# Clock.net
KiCad netlist of a schematic drawn in EAGLE
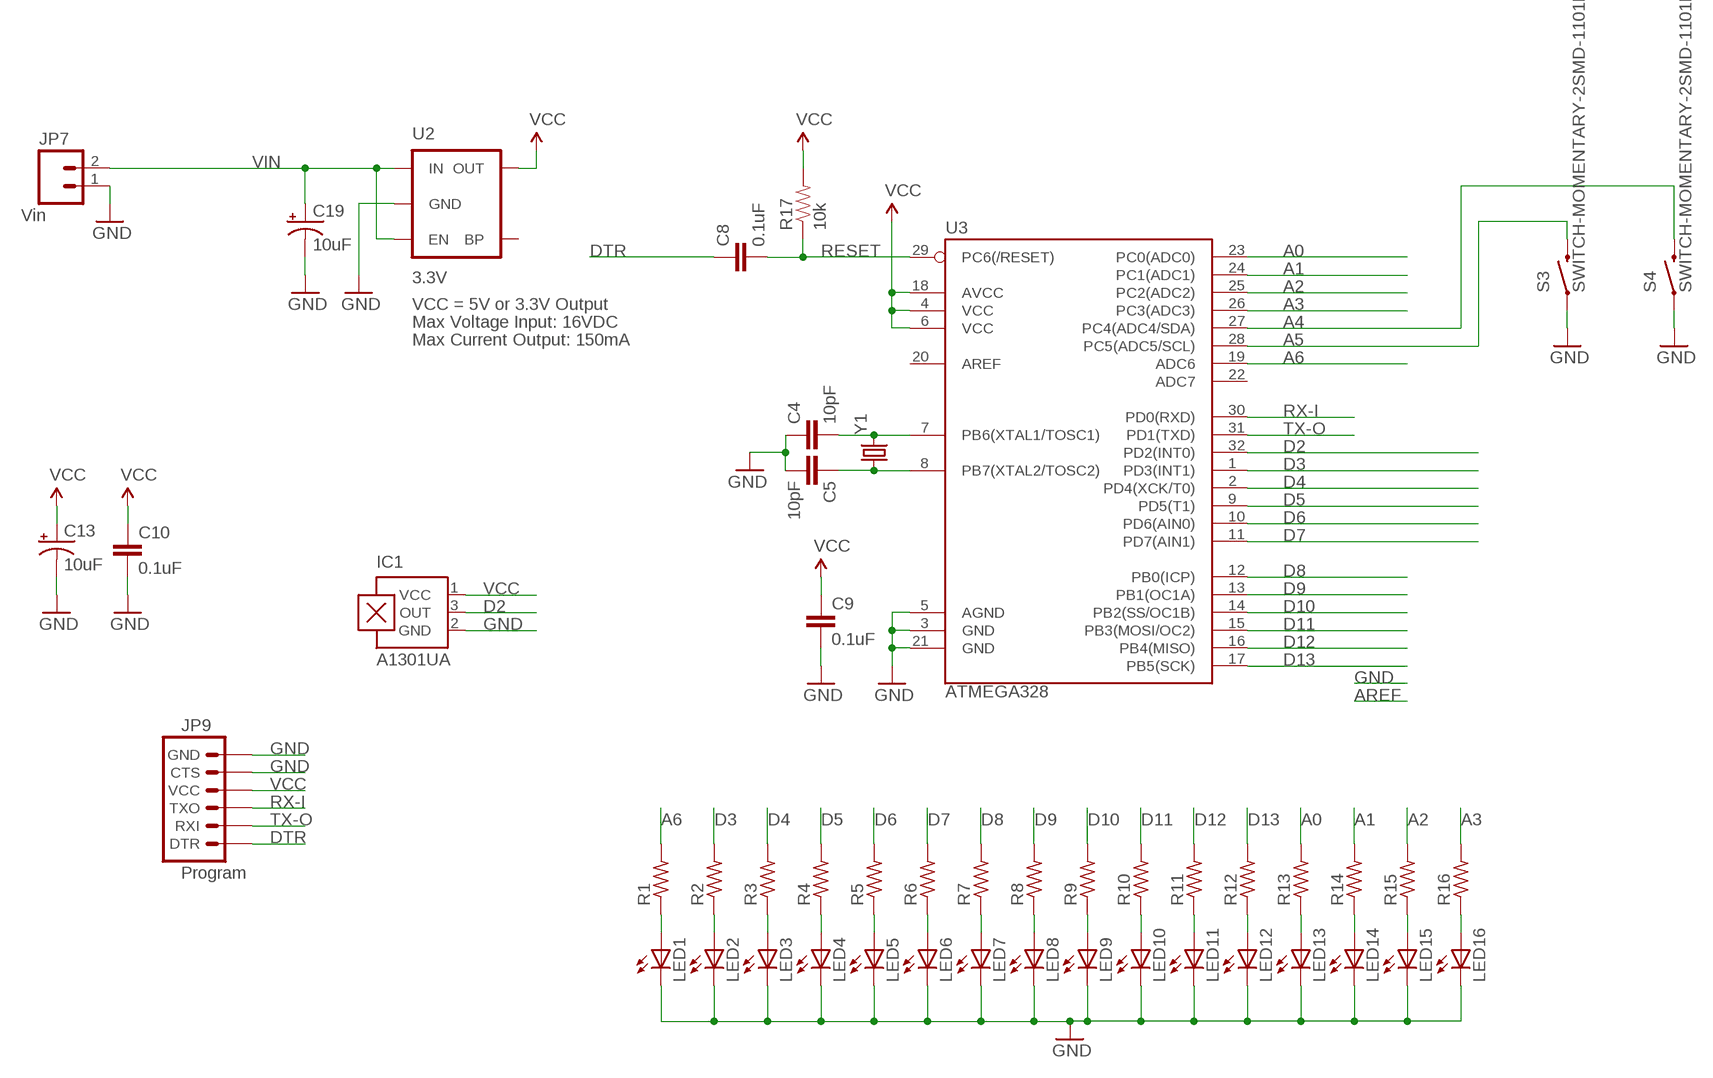
[diagram p0: schematic, sheet 1]

(export (version "E")
  (design (tool "Eeschema 10.0.6"))
  (components
    (comp (ref "C4")
      (value "10pF")
      (footprint "eagle-import:0603-CAP")
      (libsource (lib "eagle-import") (part "CAP0603-CAP"))
    )
    (comp (ref "C5")
      (value "10pF")
      (footprint "eagle-import:0603-CAP")
      (libsource (lib "eagle-import") (part "CAP0603-CAP"))
    )
    (comp (ref "C8")
      (value "0.1uF")
      (footprint "eagle-import:0603-CAP")
      (libsource (lib "eagle-import") (part "CAP0603-CAP"))
    )
    (comp (ref "C9")
      (value "0.1uF")
      (footprint "eagle-import:0603-CAP")
      (libsource (lib "eagle-import") (part "CAP0603-CAP"))
    )
    (comp (ref "C10")
      (value "0.1uF")
      (footprint "eagle-import:0603-CAP")
      (libsource (lib "eagle-import") (part "CAP0603-CAP"))
    )
    (comp (ref "C13")
      (value "10uF")
      (footprint "eagle-import:EIA3216")
      (libsource (lib "eagle-import") (part "CAP_POL1206"))
    )
    (comp (ref "C19")
      (value "10uF")
      (footprint "eagle-import:EIA3216")
      (libsource (lib "eagle-import") (part "CAP_POL1206"))
    )
    (comp (ref "IC1")
      (value "A1301UA")
      (footprint "eagle-import:SIP3-UA")
      (fields (field (name "MF") "ALLEGRO MICROSYSTEMS, INC.") (field (name "MPN") "A1301EUA-T"))
      (libsource (lib "eagle-import") (part "A13?UA01"))
    )
    (comp (ref "JP7")
      (value "Vin")
      (footprint "eagle-import:1X02")
      (libsource (lib "eagle-import") (part "M02PTH"))
    )
    (comp (ref "JP9")
      (value "Program")
      (footprint "eagle-import:1X06-SMD")
      (libsource (lib "eagle-import") (part "ARDUINO_SERIAL_PROGRAMSMD"))
    )
    (comp (ref "LED1")
      (value "LEDCHIPLED_1206")
      (footprint "eagle-import:CHIPLED_1206")
      (libsource (lib "eagle-import") (part "LEDCHIPLED_1206"))
    )
    (comp (ref "LED2")
      (value "LEDCHIPLED_1206")
      (footprint "eagle-import:CHIPLED_1206")
      (libsource (lib "eagle-import") (part "LEDCHIPLED_1206"))
    )
    (comp (ref "LED3")
      (value "LEDCHIPLED_1206")
      (footprint "eagle-import:CHIPLED_1206")
      (libsource (lib "eagle-import") (part "LEDCHIPLED_1206"))
    )
    (comp (ref "LED4")
      (value "LEDCHIPLED_1206")
      (footprint "eagle-import:CHIPLED_1206")
      (libsource (lib "eagle-import") (part "LEDCHIPLED_1206"))
    )
    (comp (ref "LED5")
      (value "LEDCHIPLED_1206")
      (footprint "eagle-import:CHIPLED_1206")
      (libsource (lib "eagle-import") (part "LEDCHIPLED_1206"))
    )
    (comp (ref "LED6")
      (value "LEDCHIPLED_1206")
      (footprint "eagle-import:CHIPLED_1206")
      (libsource (lib "eagle-import") (part "LEDCHIPLED_1206"))
    )
    (comp (ref "LED7")
      (value "LEDCHIPLED_1206")
      (footprint "eagle-import:CHIPLED_1206")
      (libsource (lib "eagle-import") (part "LEDCHIPLED_1206"))
    )
    (comp (ref "LED8")
      (value "LEDCHIPLED_1206")
      (footprint "eagle-import:CHIPLED_1206")
      (libsource (lib "eagle-import") (part "LEDCHIPLED_1206"))
    )
    (comp (ref "LED9")
      (value "LEDCHIPLED_1206")
      (footprint "eagle-import:CHIPLED_1206")
      (libsource (lib "eagle-import") (part "LEDCHIPLED_1206"))
    )
    (comp (ref "LED10")
      (value "LEDCHIPLED_1206")
      (footprint "eagle-import:CHIPLED_1206")
      (libsource (lib "eagle-import") (part "LEDCHIPLED_1206"))
    )
    (comp (ref "LED11")
      (value "LEDCHIPLED_1206")
      (footprint "eagle-import:CHIPLED_1206")
      (libsource (lib "eagle-import") (part "LEDCHIPLED_1206"))
    )
    (comp (ref "LED12")
      (value "LEDCHIPLED_1206")
      (footprint "eagle-import:CHIPLED_1206")
      (libsource (lib "eagle-import") (part "LEDCHIPLED_1206"))
    )
    (comp (ref "LED13")
      (value "LEDCHIPLED_1206")
      (footprint "eagle-import:CHIPLED_1206")
      (libsource (lib "eagle-import") (part "LEDCHIPLED_1206"))
    )
    (comp (ref "LED14")
      (value "LEDCHIPLED_1206")
      (footprint "eagle-import:CHIPLED_1206")
      (libsource (lib "eagle-import") (part "LEDCHIPLED_1206"))
    )
    (comp (ref "LED15")
      (value "LEDCHIPLED_1206")
      (footprint "eagle-import:CHIPLED_1206")
      (libsource (lib "eagle-import") (part "LEDCHIPLED_1206"))
    )
    (comp (ref "LED16")
      (value "LEDCHIPLED_1206")
      (footprint "eagle-import:CHIPLED_1206")
      (libsource (lib "eagle-import") (part "LEDCHIPLED_1206"))
    )
    (comp (ref "R1")
      (value "R-US_R0603")
      (footprint "eagle-import:R0603")
      (libsource (lib "eagle-import") (part "R-US_R0603"))
    )
    (comp (ref "R2")
      (value "R-US_R0603")
      (footprint "eagle-import:R0603")
      (libsource (lib "eagle-import") (part "R-US_R0603"))
    )
    (comp (ref "R3")
      (value "R-US_R0603")
      (footprint "eagle-import:R0603")
      (libsource (lib "eagle-import") (part "R-US_R0603"))
    )
    (comp (ref "R4")
      (value "R-US_R0603")
      (footprint "eagle-import:R0603")
      (libsource (lib "eagle-import") (part "R-US_R0603"))
    )
    (comp (ref "R5")
      (value "R-US_R0603")
      (footprint "eagle-import:R0603")
      (libsource (lib "eagle-import") (part "R-US_R0603"))
    )
    (comp (ref "R6")
      (value "R-US_R0603")
      (footprint "eagle-import:R0603")
      (libsource (lib "eagle-import") (part "R-US_R0603"))
    )
    (comp (ref "R7")
      (value "R-US_R0603")
      (footprint "eagle-import:R0603")
      (libsource (lib "eagle-import") (part "R-US_R0603"))
    )
    (comp (ref "R8")
      (value "R-US_R0603")
      (footprint "eagle-import:R0603")
      (libsource (lib "eagle-import") (part "R-US_R0603"))
    )
    (comp (ref "R9")
      (value "R-US_R0603")
      (footprint "eagle-import:R0603")
      (libsource (lib "eagle-import") (part "R-US_R0603"))
    )
    (comp (ref "R10")
      (value "R-US_R0603")
      (footprint "eagle-import:R0603")
      (libsource (lib "eagle-import") (part "R-US_R0603"))
    )
    (comp (ref "R11")
      (value "R-US_R0603")
      (footprint "eagle-import:R0603")
      (libsource (lib "eagle-import") (part "R-US_R0603"))
    )
    (comp (ref "R12")
      (value "R-US_R0603")
      (footprint "eagle-import:R0603")
      (libsource (lib "eagle-import") (part "R-US_R0603"))
    )
    (comp (ref "R13")
      (value "R-US_R0603")
      (footprint "eagle-import:R0603")
      (libsource (lib "eagle-import") (part "R-US_R0603"))
    )
    (comp (ref "R14")
      (value "R-US_R0603")
      (footprint "eagle-import:R0603")
      (libsource (lib "eagle-import") (part "R-US_R0603"))
    )
    (comp (ref "R15")
      (value "R-US_R0603")
      (footprint "eagle-import:R0603")
      (libsource (lib "eagle-import") (part "R-US_R0603"))
    )
    (comp (ref "R16")
      (value "R-US_R0603")
      (footprint "eagle-import:R0603")
      (libsource (lib "eagle-import") (part "R-US_R0603"))
    )
    (comp (ref "R17")
      (value "10k")
      (footprint "eagle-import:0603-RES")
      (libsource (lib "eagle-import") (part "RESISTOR0603-RES"))
    )
    (comp (ref "S3")
      (value "SWITCH-MOMENTARY-2SMD-1101NE")
      (footprint "eagle-import:TACTILE-SWITCH-1101NE")
      (libsource (lib "eagle-import") (part "SWITCH-MOMENTARY-2SMD-1101NE"))
    )
    (comp (ref "S4")
      (value "SWITCH-MOMENTARY-2SMD-1101NE")
      (footprint "eagle-import:TACTILE-SWITCH-1101NE")
      (libsource (lib "eagle-import") (part "SWITCH-MOMENTARY-2SMD-1101NE"))
    )
    (comp (ref "U2")
      (value "3.3V")
      (footprint "eagle-import:SOT23-5")
      (libsource (lib "eagle-import") (part "V_REG_LDOSMD"))
    )
    (comp (ref "U3")
      (value "ATMEGA328")
      (footprint "eagle-import:TQFP32-08")
      (libsource (lib "eagle-import") (part "ATMEGA168"))
    )
    (comp (ref "Y1")
      (value "CRYSTAL5X3")
      (footprint "eagle-import:CRYSTAL-SMD-5X3")
      (libsource (lib "eagle-import") (part "CRYSTAL5X3"))
    )
  )
  (nets
    (net (code "1") (name "/A0") (class "Default")
      (node (ref "R13") (pin "2") (pinfunction "2_2") (pintype "passive"))
      (node (ref "U3") (pin "23") (pinfunction "PC0(ADC0)_23") (pintype "bidirectional"))
    )
    (net (code "2") (name "/A1") (class "Default")
      (node (ref "R14") (pin "2") (pinfunction "2_2") (pintype "passive"))
      (node (ref "U3") (pin "24") (pinfunction "PC1(ADC1)_24") (pintype "bidirectional"))
    )
    (net (code "3") (name "/A2") (class "Default")
      (node (ref "R15") (pin "2") (pinfunction "2_2") (pintype "passive"))
      (node (ref "U3") (pin "25") (pinfunction "PC2(ADC2)_25") (pintype "bidirectional"))
    )
    (net (code "4") (name "/A3") (class "Default")
      (node (ref "R16") (pin "2") (pinfunction "2_2") (pintype "passive"))
      (node (ref "U3") (pin "26") (pinfunction "PC3(ADC3)_26") (pintype "bidirectional"))
    )
    (net (code "5") (name "/A4") (class "Default")
      (node (ref "S4") (pin "2") (pinfunction "2_2") (pintype "passive"))
      (node (ref "U3") (pin "27") (pinfunction "PC4(ADC4/SDA)_27") (pintype "bidirectional"))
    )
    (net (code "6") (name "/A5") (class "Default")
      (node (ref "S3") (pin "2") (pinfunction "2_2") (pintype "passive"))
      (node (ref "U3") (pin "28") (pinfunction "PC5(ADC5/SCL)_28") (pintype "bidirectional"))
    )
    (net (code "7") (name "/A6") (class "Default")
      (node (ref "R1") (pin "2") (pinfunction "2_2") (pintype "passive"))
      (node (ref "U3") (pin "19") (pinfunction "ADC6_19") (pintype "bidirectional"))
    )
    (net (code "9") (name "/D2") (class "Default")
      (node (ref "IC1") (pin "3") (pinfunction "OUT_3") (pintype "output"))
      (node (ref "U3") (pin "32") (pinfunction "PD2(INT0)_32") (pintype "bidirectional"))
    )
    (net (code "10") (name "/D3") (class "Default")
      (node (ref "R2") (pin "2") (pinfunction "2_2") (pintype "passive"))
      (node (ref "U3") (pin "1") (pinfunction "PD3(INT1)_1") (pintype "bidirectional"))
    )
    (net (code "11") (name "/D4") (class "Default")
      (node (ref "R3") (pin "2") (pinfunction "2_2") (pintype "passive"))
      (node (ref "U3") (pin "2") (pinfunction "PD4(XCK/T0)_2") (pintype "bidirectional"))
    )
    (net (code "12") (name "/D5") (class "Default")
      (node (ref "R4") (pin "2") (pinfunction "2_2") (pintype "passive"))
      (node (ref "U3") (pin "9") (pinfunction "PD5(T1)_9") (pintype "bidirectional"))
    )
    (net (code "13") (name "/D6") (class "Default")
      (node (ref "R5") (pin "2") (pinfunction "2_2") (pintype "passive"))
      (node (ref "U3") (pin "10") (pinfunction "PD6(AIN0)_10") (pintype "bidirectional"))
    )
    (net (code "14") (name "/D7") (class "Default")
      (node (ref "R6") (pin "2") (pinfunction "2_2") (pintype "passive"))
      (node (ref "U3") (pin "11") (pinfunction "PD7(AIN1)_11") (pintype "bidirectional"))
    )
    (net (code "15") (name "/D8") (class "Default")
      (node (ref "R7") (pin "2") (pinfunction "2_2") (pintype "passive"))
      (node (ref "U3") (pin "12") (pinfunction "PB0(ICP)_12") (pintype "bidirectional"))
    )
    (net (code "16") (name "/D9") (class "Default")
      (node (ref "R8") (pin "2") (pinfunction "2_2") (pintype "passive"))
      (node (ref "U3") (pin "13") (pinfunction "PB1(OC1A)_13") (pintype "bidirectional"))
    )
    (net (code "17") (name "/D10") (class "Default")
      (node (ref "R9") (pin "2") (pinfunction "2_2") (pintype "passive"))
      (node (ref "U3") (pin "14") (pinfunction "PB2(SS/OC1B)_14") (pintype "bidirectional"))
    )
    (net (code "18") (name "/D11") (class "Default")
      (node (ref "R10") (pin "2") (pinfunction "2_2") (pintype "passive"))
      (node (ref "U3") (pin "15") (pinfunction "PB3(MOSI/OC2)_15") (pintype "bidirectional"))
    )
    (net (code "19") (name "/D12") (class "Default")
      (node (ref "R11") (pin "2") (pinfunction "2_2") (pintype "passive"))
      (node (ref "U3") (pin "16") (pinfunction "PB4(MISO)_16") (pintype "bidirectional"))
    )
    (net (code "20") (name "/D13") (class "Default")
      (node (ref "R12") (pin "2") (pinfunction "2_2") (pintype "passive"))
      (node (ref "U3") (pin "17") (pinfunction "PB5(SCK)_17") (pintype "bidirectional"))
    )
    (net (code "21") (name "/DTR") (class "Default")
      (node (ref "C8") (pin "1") (pinfunction "1_1") (pintype "passive"))
      (node (ref "JP9") (pin "1") (pinfunction "DTR_1") (pintype "passive"))
    )
    (net (code "22") (name "/RESET") (class "Default")
      (node (ref "C8") (pin "2") (pinfunction "2_2") (pintype "passive"))
      (node (ref "R17") (pin "1") (pinfunction "1_1") (pintype "passive"))
      (node (ref "U3") (pin "29") (pinfunction "PC6(/RESET)_29") (pintype "bidirectional"))
    )
    (net (code "23") (name "/RX-I") (class "Default")
      (node (ref "JP9") (pin "3") (pinfunction "TXO_3") (pintype "passive"))
      (node (ref "U3") (pin "30") (pinfunction "PD0(RXD)_30") (pintype "bidirectional"))
    )
    (net (code "24") (name "/TX-O") (class "Default")
      (node (ref "JP9") (pin "2") (pinfunction "RXI_2") (pintype "passive"))
      (node (ref "U3") (pin "31") (pinfunction "PD1(TXD)_31") (pintype "bidirectional"))
    )
    (net (code "25") (name "/VIN") (class "Default")
      (node (ref "C19") (pin "A") (pinfunction "+_A") (pintype "passive"))
      (node (ref "JP7") (pin "2") (pinfunction "2_2") (pintype "passive"))
      (node (ref "U2") (pin "1") (pinfunction "IN_1") (pintype "input"))
      (node (ref "U2") (pin "3") (pinfunction "EN_3") (pintype "input"))
    )
    (net (code "26") (name "GND") (class "Default")
      (node (ref "C10") (pin "2") (pinfunction "2_2") (pintype "passive"))
      (node (ref "C13") (pin "C") (pinfunction "-_C") (pintype "passive"))
      (node (ref "C19") (pin "C") (pinfunction "-_C") (pintype "passive"))
      (node (ref "C4") (pin "1") (pinfunction "1_1") (pintype "passive"))
      (node (ref "C5") (pin "2") (pinfunction "2_2") (pintype "passive"))
      (node (ref "C9") (pin "2") (pinfunction "2_2") (pintype "passive"))
      (node (ref "IC1") (pin "2") (pinfunction "GND_2") (pintype "power_in"))
      (node (ref "JP7") (pin "1") (pinfunction "1_1") (pintype "passive"))
      (node (ref "JP9") (pin "5") (pinfunction "CTS_5") (pintype "passive"))
      (node (ref "JP9") (pin "6") (pinfunction "GND_6") (pintype "passive"))
      (node (ref "LED1") (pin "C") (pinfunction "C_C") (pintype "passive"))
      (node (ref "LED10") (pin "C") (pinfunction "C_C") (pintype "passive"))
      (node (ref "LED11") (pin "C") (pinfunction "C_C") (pintype "passive"))
      (node (ref "LED12") (pin "C") (pinfunction "C_C") (pintype "passive"))
      (node (ref "LED13") (pin "C") (pinfunction "C_C") (pintype "passive"))
      (node (ref "LED14") (pin "C") (pinfunction "C_C") (pintype "passive"))
      (node (ref "LED15") (pin "C") (pinfunction "C_C") (pintype "passive"))
      (node (ref "LED16") (pin "C") (pinfunction "C_C") (pintype "passive"))
      (node (ref "LED2") (pin "C") (pinfunction "C_C") (pintype "passive"))
      (node (ref "LED3") (pin "C") (pinfunction "C_C") (pintype "passive"))
      (node (ref "LED4") (pin "C") (pinfunction "C_C") (pintype "passive"))
      (node (ref "LED5") (pin "C") (pinfunction "C_C") (pintype "passive"))
      (node (ref "LED6") (pin "C") (pinfunction "C_C") (pintype "passive"))
      (node (ref "LED7") (pin "C") (pinfunction "C_C") (pintype "passive"))
      (node (ref "LED8") (pin "C") (pinfunction "C_C") (pintype "passive"))
      (node (ref "LED9") (pin "C") (pinfunction "C_C") (pintype "passive"))
      (node (ref "S3") (pin "1") (pinfunction "1_1") (pintype "passive"))
      (node (ref "S4") (pin "1") (pinfunction "1_1") (pintype "passive"))
      (node (ref "U2") (pin "2") (pinfunction "GND_2") (pintype "input"))
      (node (ref "U3") (pin "21") (pinfunction "GND_21") (pintype "bidirectional"))
      (node (ref "U3") (pin "3") (pinfunction "GND_3") (pintype "bidirectional"))
      (node (ref "U3") (pin "5") (pinfunction "AGND_5") (pintype "bidirectional"))
    )
    (net (code "27") (name "Net-(LED1-PadA)") (class "Default")
      (node (ref "LED1") (pin "A") (pinfunction "A_A") (pintype "passive"))
      (node (ref "R1") (pin "1") (pinfunction "1_1") (pintype "passive"))
    )
    (net (code "28") (name "Net-(LED2-PadA)") (class "Default")
      (node (ref "LED2") (pin "A") (pinfunction "A_A") (pintype "passive"))
      (node (ref "R2") (pin "1") (pinfunction "1_1") (pintype "passive"))
    )
    (net (code "29") (name "Net-(LED3-PadA)") (class "Default")
      (node (ref "LED3") (pin "A") (pinfunction "A_A") (pintype "passive"))
      (node (ref "R3") (pin "1") (pinfunction "1_1") (pintype "passive"))
    )
    (net (code "30") (name "Net-(LED4-PadA)") (class "Default")
      (node (ref "LED4") (pin "A") (pinfunction "A_A") (pintype "passive"))
      (node (ref "R4") (pin "1") (pinfunction "1_1") (pintype "passive"))
    )
    (net (code "31") (name "Net-(LED5-PadA)") (class "Default")
      (node (ref "LED5") (pin "A") (pinfunction "A_A") (pintype "passive"))
      (node (ref "R5") (pin "1") (pinfunction "1_1") (pintype "passive"))
    )
    (net (code "32") (name "Net-(LED6-PadA)") (class "Default")
      (node (ref "LED6") (pin "A") (pinfunction "A_A") (pintype "passive"))
      (node (ref "R6") (pin "1") (pinfunction "1_1") (pintype "passive"))
    )
    (net (code "33") (name "Net-(LED7-PadA)") (class "Default")
      (node (ref "LED7") (pin "A") (pinfunction "A_A") (pintype "passive"))
      (node (ref "R7") (pin "1") (pinfunction "1_1") (pintype "passive"))
    )
    (net (code "34") (name "Net-(LED8-PadA)") (class "Default")
      (node (ref "LED8") (pin "A") (pinfunction "A_A") (pintype "passive"))
      (node (ref "R8") (pin "1") (pinfunction "1_1") (pintype "passive"))
    )
    (net (code "35") (name "Net-(LED9-PadA)") (class "Default")
      (node (ref "LED9") (pin "A") (pinfunction "A_A") (pintype "passive"))
      (node (ref "R9") (pin "1") (pinfunction "1_1") (pintype "passive"))
    )
    (net (code "36") (name "Net-(LED10-PadA)") (class "Default")
      (node (ref "LED10") (pin "A") (pinfunction "A_A") (pintype "passive"))
      (node (ref "R10") (pin "1") (pinfunction "1_1") (pintype "passive"))
    )
    (net (code "37") (name "Net-(LED11-PadA)") (class "Default")
      (node (ref "LED11") (pin "A") (pinfunction "A_A") (pintype "passive"))
      (node (ref "R11") (pin "1") (pinfunction "1_1") (pintype "passive"))
    )
    (net (code "38") (name "Net-(LED12-PadA)") (class "Default")
      (node (ref "LED12") (pin "A") (pinfunction "A_A") (pintype "passive"))
      (node (ref "R12") (pin "1") (pinfunction "1_1") (pintype "passive"))
    )
    (net (code "39") (name "Net-(LED13-PadA)") (class "Default")
      (node (ref "LED13") (pin "A") (pinfunction "A_A") (pintype "passive"))
      (node (ref "R13") (pin "1") (pinfunction "1_1") (pintype "passive"))
    )
    (net (code "40") (name "Net-(LED14-PadA)") (class "Default")
      (node (ref "LED14") (pin "A") (pinfunction "A_A") (pintype "passive"))
      (node (ref "R14") (pin "1") (pinfunction "1_1") (pintype "passive"))
    )
    (net (code "41") (name "Net-(LED15-PadA)") (class "Default")
      (node (ref "LED15") (pin "A") (pinfunction "A_A") (pintype "passive"))
      (node (ref "R15") (pin "1") (pinfunction "1_1") (pintype "passive"))
    )
    (net (code "42") (name "Net-(LED16-PadA)") (class "Default")
      (node (ref "LED16") (pin "A") (pinfunction "A_A") (pintype "passive"))
      (node (ref "R16") (pin "1") (pinfunction "1_1") (pintype "passive"))
    )
    (net (code "43") (name "Net-(U3-PB6(XTAL1{slash}TOSC1))") (class "Default")
      (node (ref "C4") (pin "2") (pinfunction "2_2") (pintype "passive"))
      (node (ref "U3") (pin "7") (pinfunction "PB6(XTAL1/TOSC1)_7") (pintype "bidirectional"))
      (node (ref "Y1") (pin "3") (pinfunction "2_3") (pintype "passive"))
    )
    (net (code "44") (name "Net-(U3-PB7(XTAL2{slash}TOSC2))") (class "Default")
      (node (ref "C5") (pin "1") (pinfunction "1_1") (pintype "passive"))
      (node (ref "U3") (pin "8") (pinfunction "PB7(XTAL2/TOSC2)_8") (pintype "bidirectional"))
      (node (ref "Y1") (pin "1") (pinfunction "1_1") (pintype "passive"))
    )
    (net (code "45") (name "VCC") (class "Default")
      (node (ref "C10") (pin "1") (pinfunction "1_1") (pintype "passive"))
      (node (ref "C13") (pin "A") (pinfunction "+_A") (pintype "passive"))
      (node (ref "C9") (pin "1") (pinfunction "1_1") (pintype "passive"))
      (node (ref "IC1") (pin "1") (pinfunction "VCC_1") (pintype "power_in"))
      (node (ref "JP9") (pin "4") (pinfunction "VCC_4") (pintype "passive"))
      (node (ref "R17") (pin "2") (pinfunction "2_2") (pintype "passive"))
      (node (ref "U2") (pin "5") (pinfunction "OUT_5") (pintype "passive"))
      (node (ref "U3") (pin "18") (pinfunction "AVCC_18") (pintype "bidirectional"))
      (node (ref "U3") (pin "4") (pinfunction "VCC_4") (pintype "bidirectional"))
      (node (ref "U3") (pin "6") (pinfunction "VCC_6") (pintype "bidirectional"))
    )
    (net (code "46") (name "unconnected-(U2-BP-Pad4)") (class "Default")
      (node (ref "U2") (pin "4") (pinfunction "BP_4") (pintype "input"))
    )
    (net (code "47") (name "unconnected-(U3-ADC7-Pad22)") (class "Default")
      (node (ref "U3") (pin "22") (pinfunction "ADC7_22") (pintype "bidirectional"))
    )
    (net (code "48") (name "unconnected-(U3-AREF-Pad20)") (class "Default")
      (node (ref "U3") (pin "20") (pinfunction "AREF_20") (pintype "bidirectional"))
    )
  )
)
